# Led_Button.net
KiCad netlist of a schematic drawn in Altium Designer
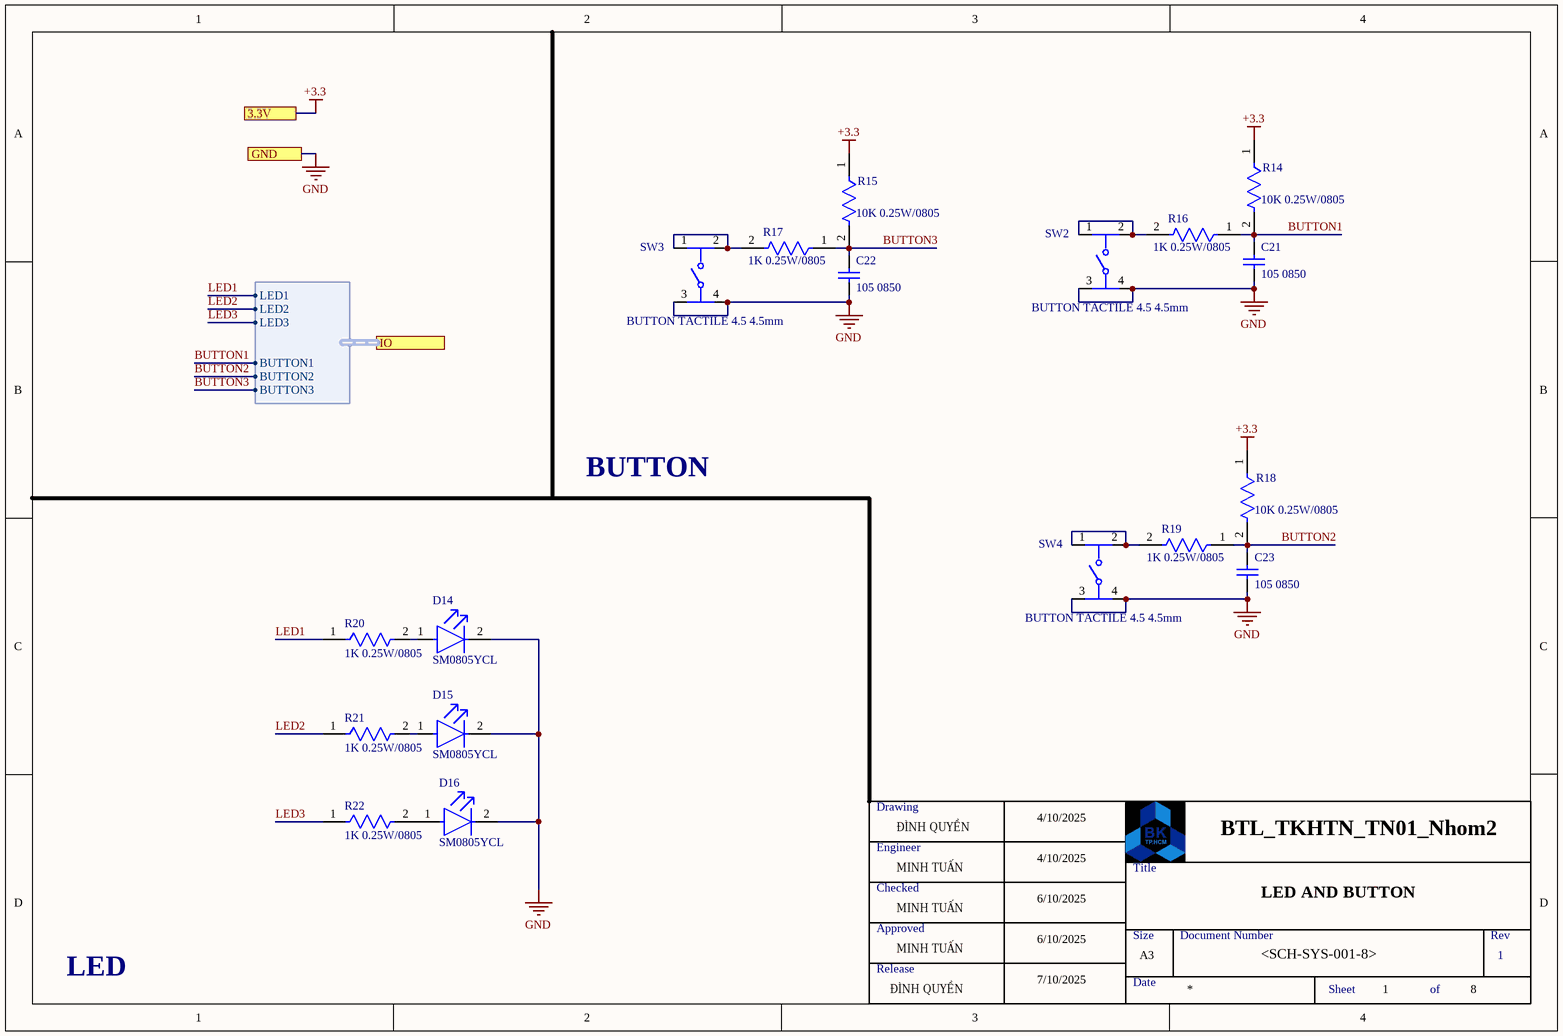
[diagram p0: Led_Button.SchDoc]

(export (version "E")
  (design (tool "Eeschema 10.0.6"))
  (components
    (comp (ref "C21")
      (value "105 0850")
      (footprint "CAPC0805(2012)145_M")
      (description "CAP 15nF 100V ±10% 0805 (2012 Metric) Thickness 1.45mm SMD")
      (fields (field (name "TOLERANCE") "Â±10%"))
      (libsource (lib "Altium Content Vault") (part "CAP"))
    )
    (comp (ref "C22")
      (value "105 0850")
      (footprint "CAPC0805(2012)145_M")
      (description "CAP 15nF 100V ±10% 0805 (2012 Metric) Thickness 1.45mm SMD")
      (fields (field (name "TOLERANCE") "Â±10%"))
      (libsource (lib "Altium Content Vault") (part "CAP"))
    )
    (comp (ref "C23")
      (value "105 0850")
      (footprint "CAPC0805(2012)145_M")
      (description "CAP 15nF 100V ±10% 0805 (2012 Metric) Thickness 1.45mm SMD")
      (fields (field (name "TOLERANCE") "Â±10%"))
      (libsource (lib "Altium Content Vault") (part "CAP"))
    )
    (comp (ref "D14")
      (value "SM0805YCL")
      (footprint "FP-SM0805YCL-MFG")
      (description "LED YELLOW CLEAR 0805 SMD")
      (libsource (lib "Altium Content Vault") (part "ab1c01a81903e929fc6c44469aada92"))
    )
    (comp (ref "D15")
      (value "SM0805YCL")
      (footprint "FP-SM0805YCL-MFG")
      (description "LED YELLOW CLEAR 0805 SMD")
      (libsource (lib "Altium Content Vault") (part "ab1c01a81903e929fc6c44469aada92"))
    )
    (comp (ref "D16")
      (value "SM0805YCL")
      (footprint "FP-SM0805YCL-MFG")
      (description "LED YELLOW CLEAR 0805 SMD")
      (libsource (lib "Altium Content Vault") (part "ab1c01a81903e929fc6c44469aada92"))
    )
    (comp (ref "R14")
      (value "10K 0.25W/0805")
      (footprint "FP-AF0805-IPC_C")
      (description "Anti-Sulfurated Chip Resistor Automotive Grade 75Ω 1% 0.125W ±100ppm/°C 0805")
      (fields (field (name "TOLERANCE") "1%"))
      (libsource (lib "Altium Content Vault") (part "1029c3af85768c4190bb7ad29bc67b5"))
    )
    (comp (ref "R15")
      (value "10K 0.25W/0805")
      (footprint "FP-AF0805-IPC_C")
      (description "Anti-Sulfurated Chip Resistor Automotive Grade 75Ω 1% 0.125W ±100ppm/°C 0805")
      (fields (field (name "TOLERANCE") "1%"))
      (libsource (lib "Altium Content Vault") (part "1029c3af85768c4190bb7ad29bc67b5"))
    )
    (comp (ref "R16")
      (value "1K 0.25W/0805")
      (footprint "FP-AF0805-IPC_C")
      (description "Anti-Sulfurated Chip Resistor Automotive Grade 75Ω 1% 0.125W ±100ppm/°C 0805")
      (fields (field (name "TOLERANCE") "1%"))
      (libsource (lib "Altium Content Vault") (part "1029c3af85768c4190bb7ad29bc67b5"))
    )
    (comp (ref "R17")
      (value "1K 0.25W/0805")
      (footprint "FP-AF0805-IPC_C")
      (description "Anti-Sulfurated Chip Resistor Automotive Grade 75Ω 1% 0.125W ±100ppm/°C 0805")
      (fields (field (name "TOLERANCE") "1%"))
      (libsource (lib "Altium Content Vault") (part "1029c3af85768c4190bb7ad29bc67b5"))
    )
    (comp (ref "R18")
      (value "10K 0.25W/0805")
      (footprint "FP-AF0805-IPC_C")
      (description "Anti-Sulfurated Chip Resistor Automotive Grade 75Ω 1% 0.125W ±100ppm/°C 0805")
      (fields (field (name "TOLERANCE") "1%"))
      (libsource (lib "Altium Content Vault") (part "1029c3af85768c4190bb7ad29bc67b5"))
    )
    (comp (ref "R19")
      (value "1K 0.25W/0805")
      (footprint "FP-AF0805-IPC_C")
      (description "Anti-Sulfurated Chip Resistor Automotive Grade 75Ω 1% 0.125W ±100ppm/°C 0805")
      (fields (field (name "TOLERANCE") "1%"))
      (libsource (lib "Altium Content Vault") (part "1029c3af85768c4190bb7ad29bc67b5"))
    )
    (comp (ref "R20")
      (value "1K 0.25W/0805")
      (footprint "FP-AF0805-IPC_C")
      (description "Anti-Sulfurated Chip Resistor Automotive Grade 75Ω 1% 0.125W ±100ppm/°C 0805")
      (fields (field (name "TOLERANCE") "1%"))
      (libsource (lib "Altium Content Vault") (part "1029c3af85768c4190bb7ad29bc67b5"))
    )
    (comp (ref "R21")
      (value "1K 0.25W/0805")
      (footprint "FP-AF0805-IPC_C")
      (description "Anti-Sulfurated Chip Resistor Automotive Grade 75Ω 1% 0.125W ±100ppm/°C 0805")
      (fields (field (name "TOLERANCE") "1%"))
      (libsource (lib "Altium Content Vault") (part "1029c3af85768c4190bb7ad29bc67b5"))
    )
    (comp (ref "R22")
      (value "1K 0.25W/0805")
      (footprint "FP-AF0805-IPC_C")
      (description "Anti-Sulfurated Chip Resistor Automotive Grade 75Ω 1% 0.125W ±100ppm/°C 0805")
      (fields (field (name "TOLERANCE") "1%"))
      (libsource (lib "Altium Content Vault") (part "1029c3af85768c4190bb7ad29bc67b5"))
    )
    (comp (ref "SW2")
      (value "BUTTON TACTILE 4.5 4.5mm")
      (footprint "FP-PTS647SK38SMTR2LFS-MFG")
      (description "TACT 4.5 X 4.5, 3.8 MM H, 2.5N,")
      (libsource (lib "Altium Content Vault") (part "1adf0dd01260c80cf25a44bfd6b99ba"))
    )
    (comp (ref "SW3")
      (value "BUTTON TACTILE 4.5 4.5mm")
      (footprint "FP-PTS647SK38SMTR2LFS-MFG")
      (description "TACT 4.5 X 4.5, 3.8 MM H, 2.5N,")
      (libsource (lib "Altium Content Vault") (part "1adf0dd01260c80cf25a44bfd6b99ba"))
    )
    (comp (ref "SW4")
      (value "BUTTON TACTILE 4.5 4.5mm")
      (footprint "FP-PTS647SK38SMTR2LFS-MFG")
      (description "TACT 4.5 X 4.5, 3.8 MM H, 2.5N,")
      (libsource (lib "Altium Content Vault") (part "1adf0dd01260c80cf25a44bfd6b99ba"))
    )
  )
  (nets
    (net (code "2") (name "+3.3") (class "Default")
      (node (ref "R14") (pin "1") (pinfunction "1_1") (pintype "passive"))
      (node (ref "R15") (pin "1") (pinfunction "1_1") (pintype "passive"))
      (node (ref "R18") (pin "1") (pinfunction "1_1") (pintype "passive"))
    )
    (net (code "3") (name "/BUTTON1") (class "Default")
      (node (ref "C21") (pin "2") (pinfunction "2_2") (pintype "passive"))
      (node (ref "R14") (pin "2") (pinfunction "2_2") (pintype "passive"))
      (node (ref "R16") (pin "1") (pinfunction "1_1") (pintype "passive"))
    )
    (net (code "4") (name "/BUTTON2") (class "Default")
      (node (ref "C23") (pin "2") (pinfunction "2_2") (pintype "passive"))
      (node (ref "R18") (pin "2") (pinfunction "2_2") (pintype "passive"))
      (node (ref "R19") (pin "1") (pinfunction "1_1") (pintype "passive"))
    )
    (net (code "5") (name "/BUTTON3") (class "Default")
      (node (ref "C22") (pin "2") (pinfunction "2_2") (pintype "passive"))
      (node (ref "R15") (pin "2") (pinfunction "2_2") (pintype "passive"))
      (node (ref "R17") (pin "1") (pinfunction "1_1") (pintype "passive"))
    )
    (net (code "6") (name "/LED1") (class "Default")
      (node (ref "R20") (pin "1") (pinfunction "1_1") (pintype "passive"))
    )
    (net (code "7") (name "/LED2") (class "Default")
      (node (ref "R21") (pin "1") (pinfunction "1_1") (pintype "passive"))
    )
    (net (code "8") (name "/LED3") (class "Default")
      (node (ref "R22") (pin "1") (pinfunction "1_1") (pintype "passive"))
    )
    (net (code "10") (name "GND") (class "Default")
      (node (ref "C21") (pin "1") (pinfunction "1_1") (pintype "passive"))
      (node (ref "C22") (pin "1") (pinfunction "1_1") (pintype "passive"))
      (node (ref "C23") (pin "1") (pinfunction "1_1") (pintype "passive"))
      (node (ref "D14") (pin "2") (pinfunction "C_2") (pintype "passive"))
      (node (ref "D15") (pin "2") (pinfunction "C_2") (pintype "passive"))
      (node (ref "D16") (pin "2") (pinfunction "C_2") (pintype "passive"))
      (node (ref "SW2") (pin "3") (pinfunction "3_3") (pintype "passive"))
      (node (ref "SW2") (pin "4") (pinfunction "4_4") (pintype "passive"))
      (node (ref "SW3") (pin "3") (pinfunction "3_3") (pintype "passive"))
      (node (ref "SW3") (pin "4") (pinfunction "4_4") (pintype "passive"))
      (node (ref "SW4") (pin "3") (pinfunction "3_3") (pintype "passive"))
      (node (ref "SW4") (pin "4") (pinfunction "4_4") (pintype "passive"))
    )
    (net (code "11") (name "Net-(D14-A)") (class "Default")
      (node (ref "D14") (pin "1") (pinfunction "A_1") (pintype "passive"))
      (node (ref "R20") (pin "2") (pinfunction "2_2") (pintype "passive"))
    )
    (net (code "12") (name "Net-(D15-A)") (class "Default")
      (node (ref "D15") (pin "1") (pinfunction "A_1") (pintype "passive"))
      (node (ref "R21") (pin "2") (pinfunction "2_2") (pintype "passive"))
    )
    (net (code "13") (name "Net-(D16-A)") (class "Default")
      (node (ref "D16") (pin "1") (pinfunction "A_1") (pintype "passive"))
      (node (ref "R22") (pin "2") (pinfunction "2_2") (pintype "passive"))
    )
    (net (code "14") (name "Net-(R16-Pad2)") (class "Default")
      (node (ref "R16") (pin "2") (pinfunction "2_2") (pintype "passive"))
      (node (ref "SW2") (pin "1") (pinfunction "1_1") (pintype "passive"))
      (node (ref "SW2") (pin "2") (pinfunction "2_2") (pintype "passive"))
    )
    (net (code "15") (name "Net-(R17-Pad2)") (class "Default")
      (node (ref "R17") (pin "2") (pinfunction "2_2") (pintype "passive"))
      (node (ref "SW3") (pin "1") (pinfunction "1_1") (pintype "passive"))
      (node (ref "SW3") (pin "2") (pinfunction "2_2") (pintype "passive"))
    )
    (net (code "16") (name "Net-(R19-Pad2)") (class "Default")
      (node (ref "R19") (pin "2") (pinfunction "2_2") (pintype "passive"))
      (node (ref "SW4") (pin "1") (pinfunction "1_1") (pintype "passive"))
      (node (ref "SW4") (pin "2") (pinfunction "2_2") (pintype "passive"))
    )
  )
)
